# nano19.net
KiCad netlist of a schematic drawn in EAGLE
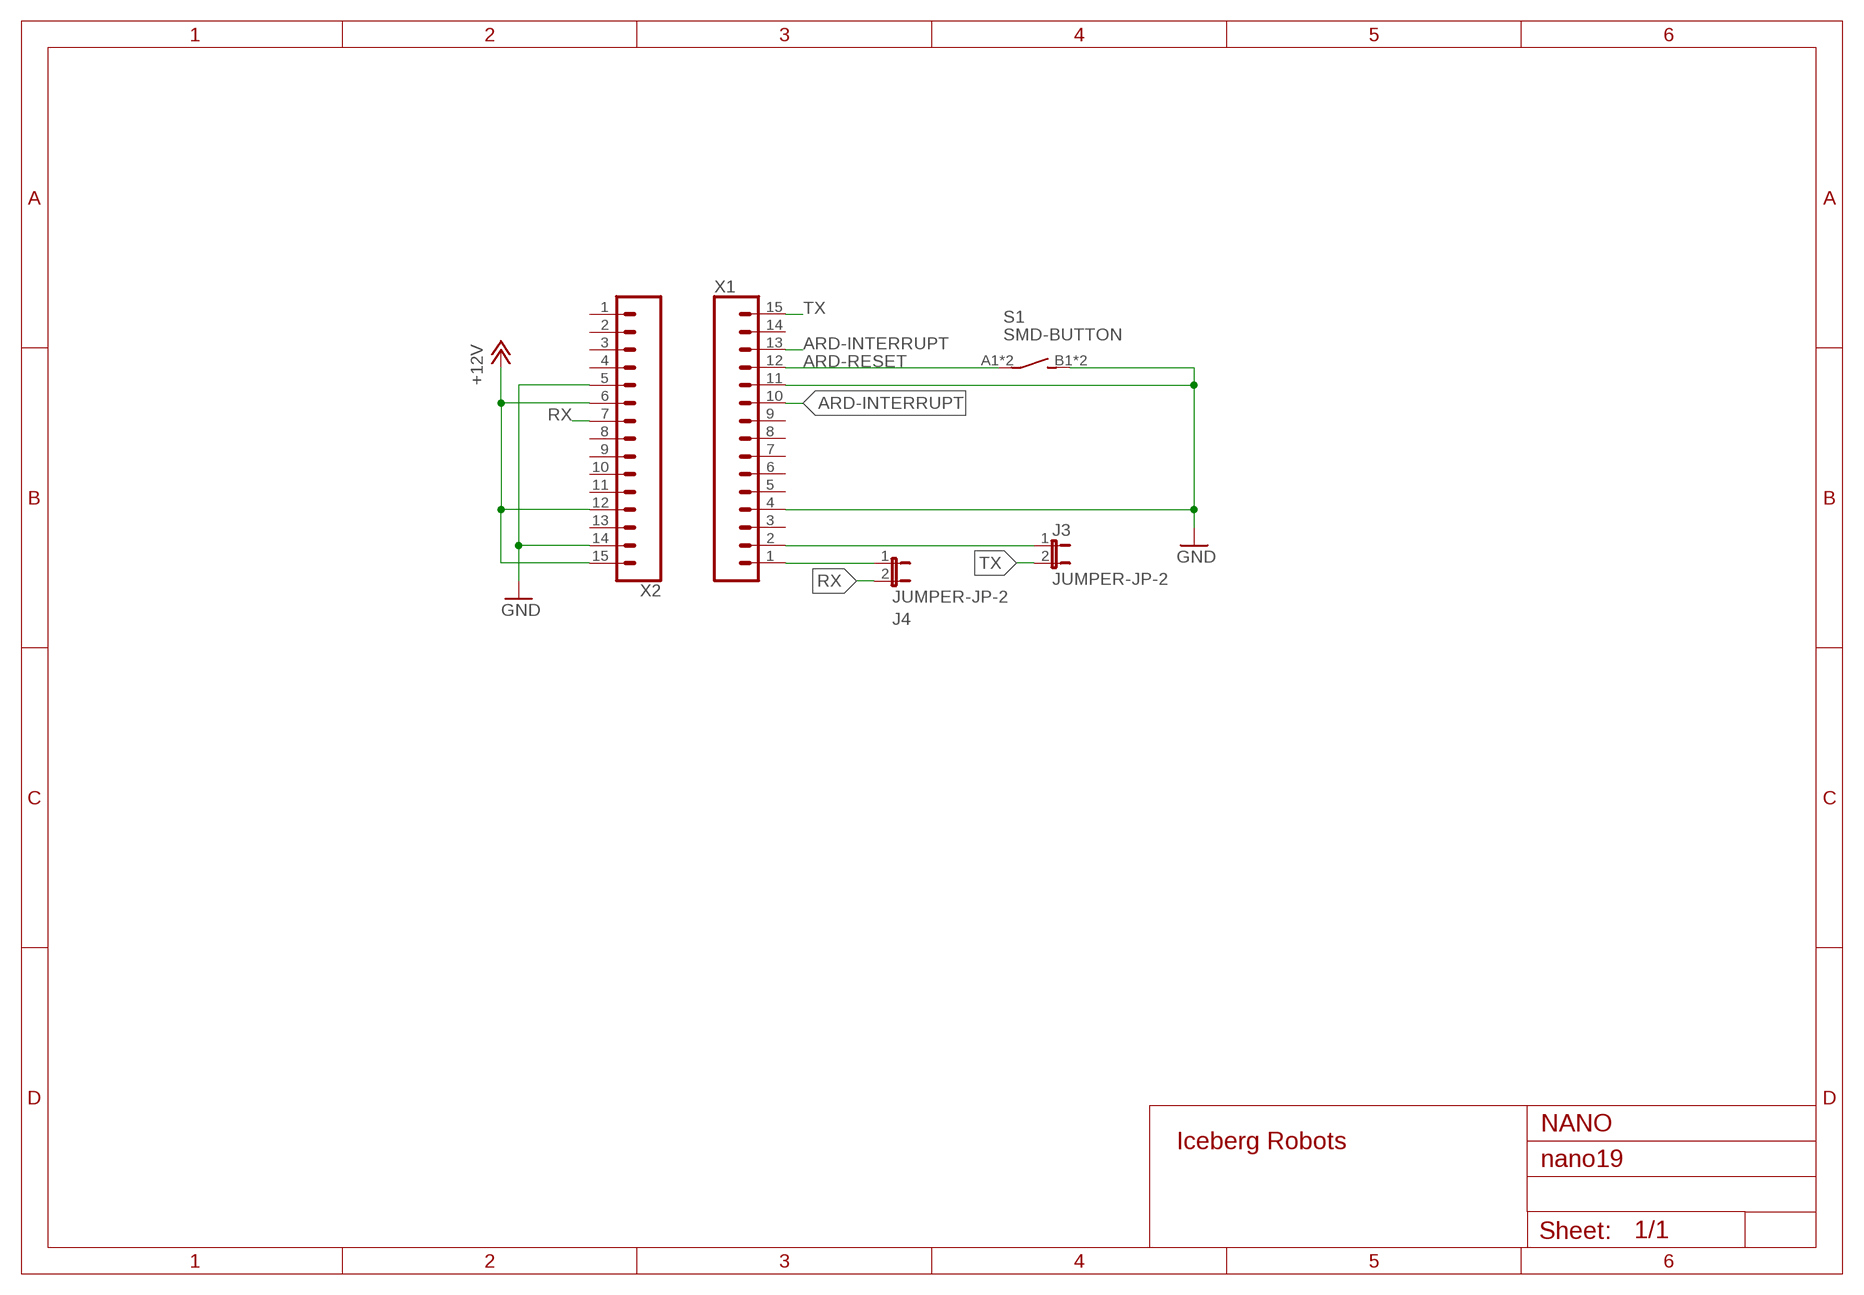
[diagram p0: schematic, sheet 1]

(export (version "E")
  (design (tool "Eeschema 10.0.6"))
  (components
    (comp (ref "J3")
      (value "JUMPER-JP-2")
      (footprint "eagle-import:JUMPER_JP1")
      (libsource (lib "eagle-import") (part "JUMPER-JP-2"))
    )
    (comp (ref "J4")
      (value "JUMPER-JP-2")
      (footprint "eagle-import:JUMPER_JP1")
      (libsource (lib "eagle-import") (part "JUMPER-JP-2"))
    )
    (comp (ref "S1")
      (value "SMD-BUTTON")
      (footprint "eagle-import:SWITCH-6MM-SMD")
      (libsource (lib "eagle-import") (part "SMD-BUTTON"))
    )
    (comp (ref "X1")
      (value "CONN_15")
      (footprint "eagle-import:1X15")
      (libsource (lib "eagle-import") (part "CONN_15"))
    )
    (comp (ref "X2")
      (value "CONN_15")
      (footprint "eagle-import:1X15")
      (libsource (lib "eagle-import") (part "CONN_15"))
    )
  )
  (nets
    (net (code "1") (name "+12V") (class "Default")
      (node (ref "X2") (pin "12") (pinfunction "12_12") (pintype "passive"))
      (node (ref "X2") (pin "15") (pinfunction "15_15") (pintype "passive"))
      (node (ref "X2") (pin "6") (pinfunction "6_6") (pintype "passive"))
    )
    (net (code "2") (name "/ARD-RESET") (class "Default")
      (node (ref "S1") (pin "A1") (pinfunction "P_A1") (pintype "passive"))
      (node (ref "S1") (pin "A2") (pinfunction "P_A2") (pintype "passive"))
      (node (ref "X1") (pin "12") (pinfunction "12_12") (pintype "passive"))
    )
    (net (code "3") (name "ARD-INTERRUPT") (class "Default")
      (node (ref "X1") (pin "10") (pinfunction "10_10") (pintype "passive"))
      (node (ref "X1") (pin "13") (pinfunction "13_13") (pintype "passive"))
    )
    (net (code "4") (name "GND") (class "Default")
      (node (ref "S1") (pin "B1") (pinfunction "S_B1") (pintype "passive"))
      (node (ref "S1") (pin "B2") (pinfunction "S_B2") (pintype "passive"))
      (node (ref "X1") (pin "11") (pinfunction "11_11") (pintype "passive"))
      (node (ref "X1") (pin "4") (pinfunction "4_4") (pintype "passive"))
      (node (ref "X2") (pin "14") (pinfunction "14_14") (pintype "passive"))
      (node (ref "X2") (pin "5") (pinfunction "5_5") (pintype "passive"))
    )
    (net (code "5") (name "Net-(J3-Pad1)") (class "Default")
      (node (ref "J3") (pin "1") (pinfunction "1_1") (pintype "passive"))
      (node (ref "X1") (pin "2") (pinfunction "2_2") (pintype "passive"))
    )
    (net (code "6") (name "Net-(J4-Pad1)") (class "Default")
      (node (ref "J4") (pin "1") (pinfunction "1_1") (pintype "passive"))
      (node (ref "X1") (pin "1") (pinfunction "1_1") (pintype "passive"))
    )
    (net (code "7") (name "RX") (class "Default")
      (node (ref "J4") (pin "2") (pinfunction "2_2") (pintype "passive"))
      (node (ref "X2") (pin "7") (pinfunction "7_7") (pintype "passive"))
    )
    (net (code "8") (name "TX") (class "Default")
      (node (ref "J3") (pin "2") (pinfunction "2_2") (pintype "passive"))
      (node (ref "X1") (pin "15") (pinfunction "15_15") (pintype "passive"))
    )
    (net (code "9") (name "unconnected-(X1-Pad3)") (class "Default")
      (node (ref "X1") (pin "3") (pinfunction "3_3") (pintype "passive"))
    )
    (net (code "10") (name "unconnected-(X1-Pad5)") (class "Default")
      (node (ref "X1") (pin "5") (pinfunction "5_5") (pintype "passive"))
    )
    (net (code "11") (name "unconnected-(X1-Pad6)") (class "Default")
      (node (ref "X1") (pin "6") (pinfunction "6_6") (pintype "passive"))
    )
    (net (code "12") (name "unconnected-(X1-Pad7)") (class "Default")
      (node (ref "X1") (pin "7") (pinfunction "7_7") (pintype "passive"))
    )
    (net (code "13") (name "unconnected-(X1-Pad8)") (class "Default")
      (node (ref "X1") (pin "8") (pinfunction "8_8") (pintype "passive"))
    )
    (net (code "14") (name "unconnected-(X1-Pad9)") (class "Default")
      (node (ref "X1") (pin "9") (pinfunction "9_9") (pintype "passive"))
    )
    (net (code "15") (name "unconnected-(X1-Pad14)") (class "Default")
      (node (ref "X1") (pin "14") (pinfunction "14_14") (pintype "passive"))
    )
    (net (code "16") (name "unconnected-(X2-Pad1)") (class "Default")
      (node (ref "X2") (pin "1") (pinfunction "1_1") (pintype "passive"))
    )
    (net (code "17") (name "unconnected-(X2-Pad2)") (class "Default")
      (node (ref "X2") (pin "2") (pinfunction "2_2") (pintype "passive"))
    )
    (net (code "18") (name "unconnected-(X2-Pad3)") (class "Default")
      (node (ref "X2") (pin "3") (pinfunction "3_3") (pintype "passive"))
    )
    (net (code "19") (name "unconnected-(X2-Pad4)") (class "Default")
      (node (ref "X2") (pin "4") (pinfunction "4_4") (pintype "passive"))
    )
    (net (code "20") (name "unconnected-(X2-Pad8)") (class "Default")
      (node (ref "X2") (pin "8") (pinfunction "8_8") (pintype "passive"))
    )
    (net (code "21") (name "unconnected-(X2-Pad9)") (class "Default")
      (node (ref "X2") (pin "9") (pinfunction "9_9") (pintype "passive"))
    )
    (net (code "22") (name "unconnected-(X2-Pad10)") (class "Default")
      (node (ref "X2") (pin "10") (pinfunction "10_10") (pintype "passive"))
    )
    (net (code "23") (name "unconnected-(X2-Pad11)") (class "Default")
      (node (ref "X2") (pin "11") (pinfunction "11_11") (pintype "passive"))
    )
    (net (code "24") (name "unconnected-(X2-Pad13)") (class "Default")
      (node (ref "X2") (pin "13") (pinfunction "13_13") (pintype "passive"))
    )
  )
)
